# 2021-05-24.net
KiCad netlist of a schematic drawn in EasyEDA
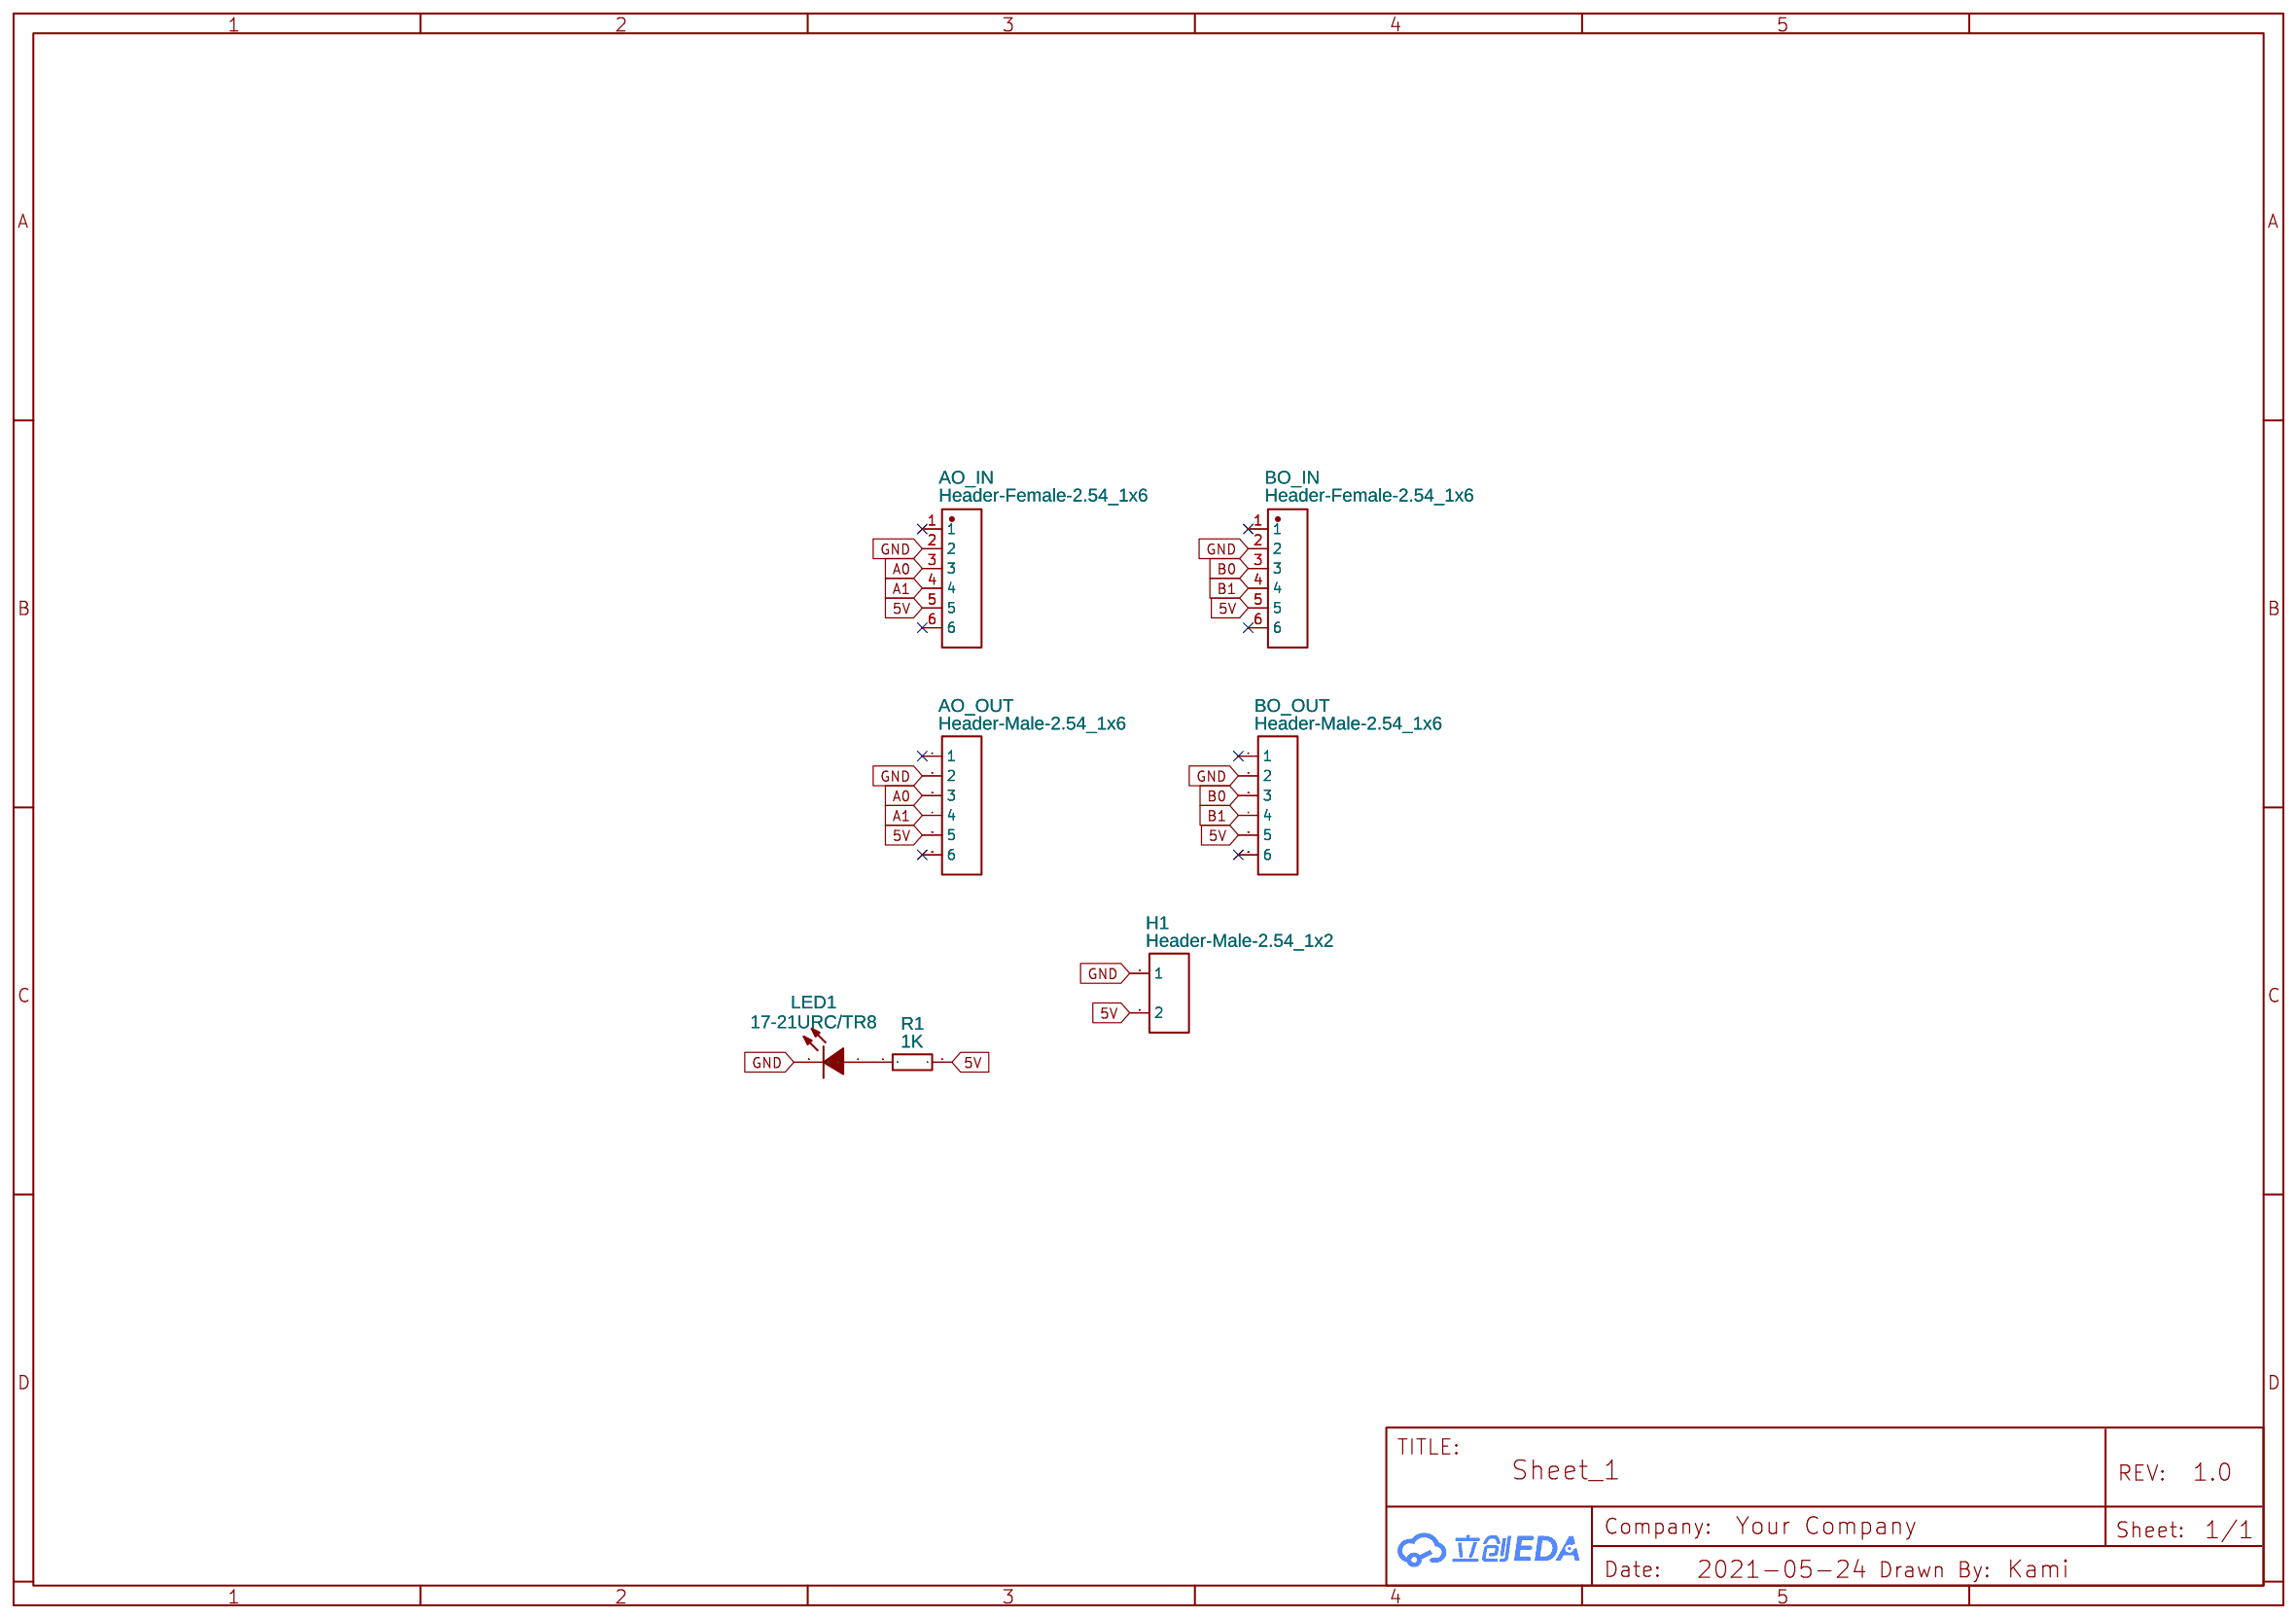
[diagram p0: schematic sheet]

(export (version "E")
  (design (tool "Eeschema 10.0.6"))
  (components
    (comp (ref "AO_IN")
      (value "Header-Female-2.54_1x6")
      (fields
        (field (name "BOM_Manufacturer Part") "Female header 1*6p")
        (field (name "BOM_Supplier Part") "C40877")
      )
      (libsource (lib "") (part "Header-Female-2.54_1x6_1"))
    )
    (comp (ref "AO_OUT")
      (value "Header-Male-2.54_1x6")
      (fields (field (name "BOM_Supplier Part") "C37208"))
      (libsource (lib "") (part "Header-Male-2.54_1x6"))
    )
    (comp (ref "BO_IN")
      (value "Header-Female-2.54_1x6")
      (fields
        (field (name "BOM_Manufacturer Part") "Female header 1*6p")
        (field (name "BOM_Supplier Part") "C40877")
      )
      (libsource (lib "") (part "Header-Female-2.54_1x6"))
    )
    (comp (ref "BO_OUT")
      (value "Header-Male-2.54_1x6")
      (fields (field (name "BOM_Supplier Part") "C37208"))
      (libsource (lib "") (part "Header-Male-2.54_1x6_1"))
    )
    (comp (ref "H1")
      (value "Header-Male-2.54_1x2")
      (fields (field (name "BOM_Manufacturer Part") "826629-2") (field (name "BOM_Supplier Part") "C86471"))
      (libsource (lib "") (part "Header-Male-2.54_1x2"))
    )
    (comp (ref "LED1")
      (value "17-21URC/TR8")
      (fields (field (name "BOM_Supplier Part") "C264414"))
      (libsource (lib "") (part "17-21URC/TR8"))
    )
    (comp (ref "R1")
      (value "1K")
      (fields
        (field (name "BOM_Manufacturer Part") "AF0805FR-071KL")
        (field (name "BOM_Supplier Part") "C192907")
      )
      (libsource (lib "") (part "AF0805FR-071KL"))
    )
  )
  (nets
    (net (code "1") (name "5V") (class "Default")
      (node (ref "AO_IN") (pin "5") (pinfunction "5_5") (pintype "unspecified"))
      (node (ref "AO_OUT") (pin "5") (pinfunction "5_5") (pintype "input"))
      (node (ref "BO_IN") (pin "5") (pinfunction "5_5") (pintype "unspecified"))
      (node (ref "BO_OUT") (pin "5") (pinfunction "5_5") (pintype "input"))
      (node (ref "H1") (pin "2") (pinfunction "2_2") (pintype "unspecified"))
      (node (ref "R1") (pin "2") (pinfunction "2_2") (pintype "unspecified"))
    )
    (net (code "2") (name "A0") (class "Default")
      (node (ref "AO_IN") (pin "3") (pinfunction "3_3") (pintype "unspecified"))
      (node (ref "AO_OUT") (pin "3") (pinfunction "3_3") (pintype "input"))
    )
    (net (code "3") (name "A1") (class "Default")
      (node (ref "AO_IN") (pin "4") (pinfunction "4_4") (pintype "unspecified"))
      (node (ref "AO_OUT") (pin "4") (pinfunction "4_4") (pintype "input"))
    )
    (net (code "4") (name "B0") (class "Default")
      (node (ref "BO_IN") (pin "3") (pinfunction "3_3") (pintype "unspecified"))
      (node (ref "BO_OUT") (pin "3") (pinfunction "3_3") (pintype "input"))
    )
    (net (code "5") (name "B1") (class "Default")
      (node (ref "BO_IN") (pin "4") (pinfunction "4_4") (pintype "unspecified"))
      (node (ref "BO_OUT") (pin "4") (pinfunction "4_4") (pintype "input"))
    )
    (net (code "6") (name "GND") (class "Default")
      (node (ref "AO_IN") (pin "2") (pinfunction "2_2") (pintype "unspecified"))
      (node (ref "AO_OUT") (pin "2") (pinfunction "2_2") (pintype "input"))
      (node (ref "BO_IN") (pin "2") (pinfunction "2_2") (pintype "unspecified"))
      (node (ref "BO_OUT") (pin "2") (pinfunction "2_2") (pintype "input"))
      (node (ref "H1") (pin "1") (pinfunction "1_1") (pintype "unspecified"))
      (node (ref "LED1") (pin "2") (pinfunction "K_2") (pintype "unspecified"))
    )
    (net (code "7") (name "Net-(LED1-A)") (class "Default")
      (node (ref "LED1") (pin "1") (pinfunction "A_1") (pintype "unspecified"))
      (node (ref "R1") (pin "1") (pinfunction "1_1") (pintype "unspecified"))
    )
    (net (code "8") (name "unconnected-(AO_IN-Pad1)") (class "Default")
      (node (ref "AO_IN") (pin "1") (pinfunction "1_1") (pintype "unspecified+no_connect"))
    )
    (net (code "9") (name "unconnected-(AO_IN-Pad6)") (class "Default")
      (node (ref "AO_IN") (pin "6") (pinfunction "6_6") (pintype "unspecified+no_connect"))
    )
    (net (code "10") (name "unconnected-(AO_OUT-Pad1)") (class "Default")
      (node (ref "AO_OUT") (pin "1") (pinfunction "1_1") (pintype "input+no_connect"))
    )
    (net (code "11") (name "unconnected-(AO_OUT-Pad6)") (class "Default")
      (node (ref "AO_OUT") (pin "6") (pinfunction "6_6") (pintype "input+no_connect"))
    )
    (net (code "12") (name "unconnected-(BO_IN-Pad1)") (class "Default")
      (node (ref "BO_IN") (pin "1") (pinfunction "1_1") (pintype "unspecified+no_connect"))
    )
    (net (code "13") (name "unconnected-(BO_IN-Pad6)") (class "Default")
      (node (ref "BO_IN") (pin "6") (pinfunction "6_6") (pintype "unspecified+no_connect"))
    )
    (net (code "14") (name "unconnected-(BO_OUT-Pad1)") (class "Default")
      (node (ref "BO_OUT") (pin "1") (pinfunction "1_1") (pintype "input+no_connect"))
    )
    (net (code "15") (name "unconnected-(BO_OUT-Pad6)") (class "Default")
      (node (ref "BO_OUT") (pin "6") (pinfunction "6_6") (pintype "input+no_connect"))
    )
  )
)
